# AINx3.net
KiCad netlist of a schematic drawn in EAGLE
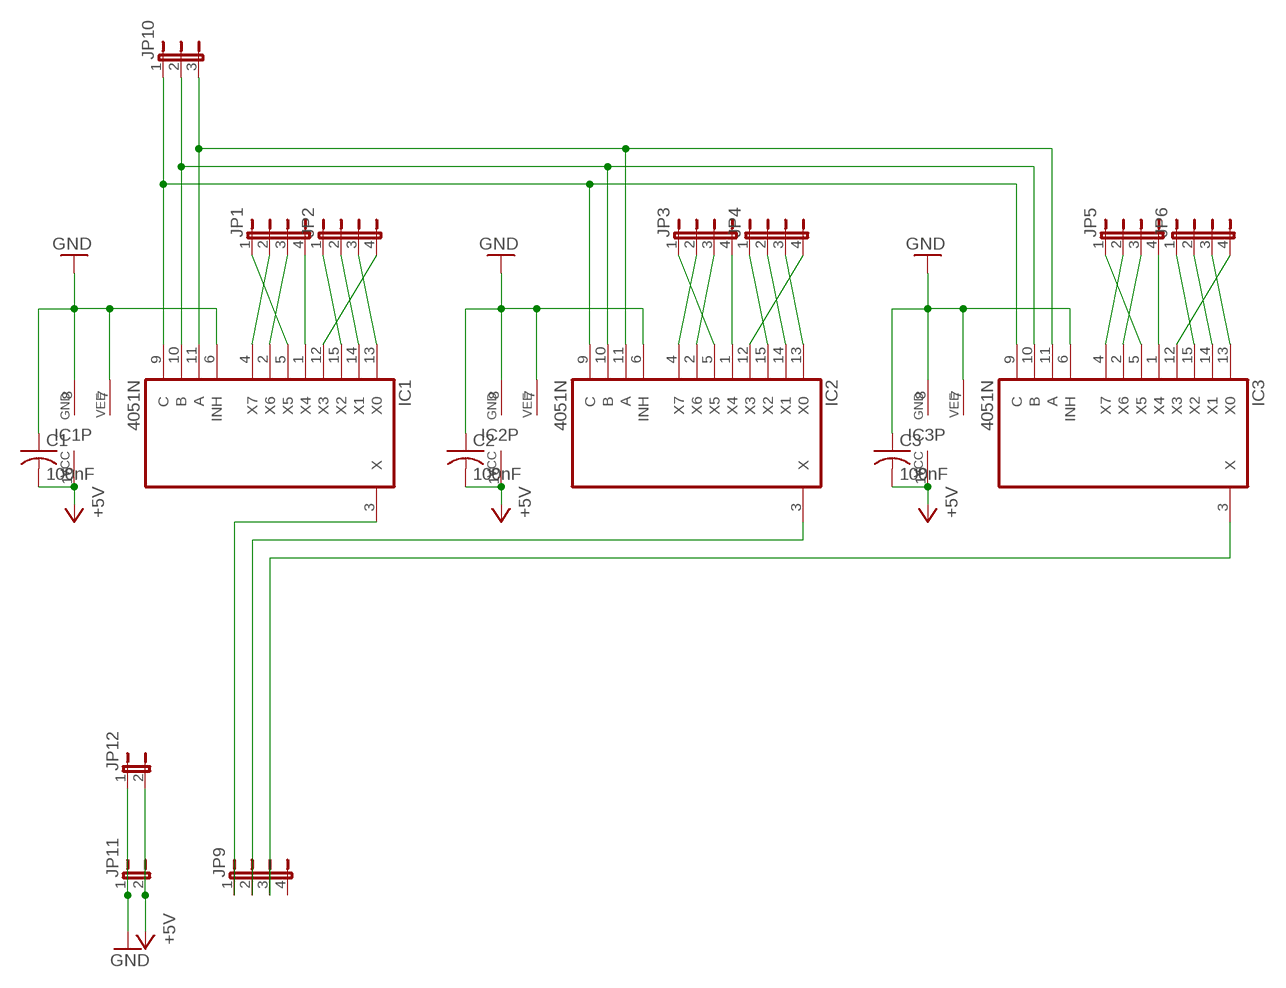
[diagram p0: schematic, sheet 1]

(export (version "E")
  (design (tool "Eeschema 10.0.6"))
  (components
    (comp (ref "C1")
      (value "100nF")
      (footprint "eagle-import:C025-025X050")
      (libsource (lib "eagle-import") (part "C-US025-025X050"))
    )
    (comp (ref "C2")
      (value "100nF")
      (footprint "eagle-import:C025-025X050")
      (libsource (lib "eagle-import") (part "C-US025-025X050"))
    )
    (comp (ref "C3")
      (value "100nF")
      (footprint "eagle-import:C025-025X050")
      (libsource (lib "eagle-import") (part "C-US025-025X050"))
    )
    (comp (ref "IC1")
      (value "4051N")
      (footprint "eagle-import:DIL16")
      (libsource (lib "eagle-import") (part "4051N"))
    )
    (comp (ref "IC2")
      (value "4051N")
      (footprint "eagle-import:DIL16")
      (libsource (lib "eagle-import") (part "4051N"))
    )
    (comp (ref "IC3")
      (value "4051N")
      (footprint "eagle-import:DIL16")
      (libsource (lib "eagle-import") (part "4051N"))
    )
    (comp (ref "JP1")
      (value "JP4E")
      (footprint "eagle-import:JP4")
      (libsource (lib "eagle-import") (part "JP4E"))
    )
    (comp (ref "JP2")
      (value "JP4E")
      (footprint "eagle-import:JP4")
      (libsource (lib "eagle-import") (part "JP4E"))
    )
    (comp (ref "JP3")
      (value "JP4E")
      (footprint "eagle-import:JP4")
      (libsource (lib "eagle-import") (part "JP4E"))
    )
    (comp (ref "JP4")
      (value "JP4E")
      (footprint "eagle-import:JP4")
      (libsource (lib "eagle-import") (part "JP4E"))
    )
    (comp (ref "JP5")
      (value "JP4E")
      (footprint "eagle-import:JP4")
      (libsource (lib "eagle-import") (part "JP4E"))
    )
    (comp (ref "JP6")
      (value "JP4E")
      (footprint "eagle-import:JP4")
      (libsource (lib "eagle-import") (part "JP4E"))
    )
    (comp (ref "JP9")
      (value "JP4E")
      (footprint "eagle-import:JP4")
      (libsource (lib "eagle-import") (part "JP4E"))
    )
    (comp (ref "JP10")
      (value "JP2E")
      (footprint "eagle-import:JP2")
      (libsource (lib "eagle-import") (part "JP2E"))
    )
    (comp (ref "JP11")
      (value "JP1E")
      (footprint "eagle-import:JP1")
      (libsource (lib "eagle-import") (part "JP1E"))
    )
    (comp (ref "JP12")
      (value "JP1E")
      (footprint "eagle-import:JP1")
      (libsource (lib "eagle-import") (part "JP1E"))
    )
  )
  (nets
    (net (code "1") (name "+5V") (class "Default")
      (node (ref "C1") (pin "2") (pinfunction "2_2") (pintype "passive"))
      (node (ref "C2") (pin "2") (pinfunction "2_2") (pintype "passive"))
      (node (ref "C3") (pin "2") (pinfunction "2_2") (pintype "passive"))
      (node (ref "IC1") (pin "16") (pinfunction "VCC_16") (pintype "power_in"))
      (node (ref "IC2") (pin "16") (pinfunction "VCC_16") (pintype "power_in"))
      (node (ref "IC3") (pin "16") (pinfunction "VCC_16") (pintype "power_in"))
      (node (ref "JP11") (pin "2") (pinfunction "2_2") (pintype "passive"))
      (node (ref "JP12") (pin "2") (pinfunction "2_2") (pintype "passive"))
    )
    (net (code "2") (name "GND") (class "Default")
      (node (ref "C1") (pin "1") (pinfunction "1_1") (pintype "passive"))
      (node (ref "C2") (pin "1") (pinfunction "1_1") (pintype "passive"))
      (node (ref "C3") (pin "1") (pinfunction "1_1") (pintype "passive"))
      (node (ref "IC1") (pin "6") (pinfunction "INH_6") (pintype "input"))
      (node (ref "IC1") (pin "7") (pinfunction "VEE_7") (pintype "power_in"))
      (node (ref "IC1") (pin "8") (pinfunction "GND_8") (pintype "power_in"))
      (node (ref "IC2") (pin "6") (pinfunction "INH_6") (pintype "input"))
      (node (ref "IC2") (pin "7") (pinfunction "VEE_7") (pintype "power_in"))
      (node (ref "IC2") (pin "8") (pinfunction "GND_8") (pintype "power_in"))
      (node (ref "IC3") (pin "6") (pinfunction "INH_6") (pintype "input"))
      (node (ref "IC3") (pin "7") (pinfunction "VEE_7") (pintype "power_in"))
      (node (ref "IC3") (pin "8") (pinfunction "GND_8") (pintype "power_in"))
      (node (ref "JP11") (pin "1") (pinfunction "1_1") (pintype "passive"))
      (node (ref "JP12") (pin "1") (pinfunction "1_1") (pintype "passive"))
    )
    (net (code "3") (name "Net-(IC1A-A)") (class "Default")
      (node (ref "IC1") (pin "11") (pinfunction "A_11") (pintype "input"))
      (node (ref "IC2") (pin "11") (pinfunction "A_11") (pintype "input"))
      (node (ref "IC3") (pin "11") (pinfunction "A_11") (pintype "input"))
      (node (ref "JP10") (pin "3") (pinfunction "3_3") (pintype "passive"))
    )
    (net (code "4") (name "Net-(IC1A-B)") (class "Default")
      (node (ref "IC1") (pin "10") (pinfunction "B_10") (pintype "input"))
      (node (ref "IC2") (pin "10") (pinfunction "B_10") (pintype "input"))
      (node (ref "IC3") (pin "10") (pinfunction "B_10") (pintype "input"))
      (node (ref "JP10") (pin "2") (pinfunction "2_2") (pintype "passive"))
    )
    (net (code "5") (name "Net-(IC1A-C)") (class "Default")
      (node (ref "IC1") (pin "9") (pinfunction "C_9") (pintype "input"))
      (node (ref "IC2") (pin "9") (pinfunction "C_9") (pintype "input"))
      (node (ref "IC3") (pin "9") (pinfunction "C_9") (pintype "input"))
      (node (ref "JP10") (pin "1") (pinfunction "1_1") (pintype "passive"))
    )
    (net (code "6") (name "Net-(IC1A-X)") (class "Default")
      (node (ref "IC1") (pin "3") (pinfunction "X_3") (pintype "bidirectional"))
      (node (ref "JP9") (pin "1") (pinfunction "1_1") (pintype "passive"))
    )
    (net (code "7") (name "Net-(IC1A-X0)") (class "Default")
      (node (ref "IC1") (pin "13") (pinfunction "X0_13") (pintype "bidirectional"))
      (node (ref "JP2") (pin "3") (pinfunction "3_3") (pintype "passive"))
    )
    (net (code "8") (name "Net-(IC1A-X1)") (class "Default")
      (node (ref "IC1") (pin "14") (pinfunction "X1_14") (pintype "bidirectional"))
      (node (ref "JP2") (pin "2") (pinfunction "2_2") (pintype "passive"))
    )
    (net (code "9") (name "Net-(IC1A-X2)") (class "Default")
      (node (ref "IC1") (pin "15") (pinfunction "X2_15") (pintype "bidirectional"))
      (node (ref "JP2") (pin "1") (pinfunction "1_1") (pintype "passive"))
    )
    (net (code "10") (name "Net-(IC1A-X3)") (class "Default")
      (node (ref "IC1") (pin "12") (pinfunction "X3_12") (pintype "bidirectional"))
      (node (ref "JP2") (pin "4") (pinfunction "4_4") (pintype "passive"))
    )
    (net (code "11") (name "Net-(IC1A-X4)") (class "Default")
      (node (ref "IC1") (pin "1") (pinfunction "X4_1") (pintype "bidirectional"))
      (node (ref "JP1") (pin "4") (pinfunction "4_4") (pintype "passive"))
    )
    (net (code "12") (name "Net-(IC1A-X5)") (class "Default")
      (node (ref "IC1") (pin "5") (pinfunction "X5_5") (pintype "bidirectional"))
      (node (ref "JP1") (pin "1") (pinfunction "1_1") (pintype "passive"))
    )
    (net (code "13") (name "Net-(IC1A-X6)") (class "Default")
      (node (ref "IC1") (pin "2") (pinfunction "X6_2") (pintype "bidirectional"))
      (node (ref "JP1") (pin "3") (pinfunction "3_3") (pintype "passive"))
    )
    (net (code "14") (name "Net-(IC1A-X7)") (class "Default")
      (node (ref "IC1") (pin "4") (pinfunction "X7_4") (pintype "bidirectional"))
      (node (ref "JP1") (pin "2") (pinfunction "2_2") (pintype "passive"))
    )
    (net (code "15") (name "Net-(IC2A-X)") (class "Default")
      (node (ref "IC2") (pin "3") (pinfunction "X_3") (pintype "bidirectional"))
      (node (ref "JP9") (pin "2") (pinfunction "2_2") (pintype "passive"))
    )
    (net (code "16") (name "Net-(IC2A-X0)") (class "Default")
      (node (ref "IC2") (pin "13") (pinfunction "X0_13") (pintype "bidirectional"))
      (node (ref "JP4") (pin "3") (pinfunction "3_3") (pintype "passive"))
    )
    (net (code "17") (name "Net-(IC2A-X1)") (class "Default")
      (node (ref "IC2") (pin "14") (pinfunction "X1_14") (pintype "bidirectional"))
      (node (ref "JP4") (pin "2") (pinfunction "2_2") (pintype "passive"))
    )
    (net (code "18") (name "Net-(IC2A-X2)") (class "Default")
      (node (ref "IC2") (pin "15") (pinfunction "X2_15") (pintype "bidirectional"))
      (node (ref "JP4") (pin "1") (pinfunction "1_1") (pintype "passive"))
    )
    (net (code "19") (name "Net-(IC2A-X3)") (class "Default")
      (node (ref "IC2") (pin "12") (pinfunction "X3_12") (pintype "bidirectional"))
      (node (ref "JP4") (pin "4") (pinfunction "4_4") (pintype "passive"))
    )
    (net (code "20") (name "Net-(IC2A-X4)") (class "Default")
      (node (ref "IC2") (pin "1") (pinfunction "X4_1") (pintype "bidirectional"))
      (node (ref "JP3") (pin "4") (pinfunction "4_4") (pintype "passive"))
    )
    (net (code "21") (name "Net-(IC2A-X5)") (class "Default")
      (node (ref "IC2") (pin "5") (pinfunction "X5_5") (pintype "bidirectional"))
      (node (ref "JP3") (pin "1") (pinfunction "1_1") (pintype "passive"))
    )
    (net (code "22") (name "Net-(IC2A-X6)") (class "Default")
      (node (ref "IC2") (pin "2") (pinfunction "X6_2") (pintype "bidirectional"))
      (node (ref "JP3") (pin "3") (pinfunction "3_3") (pintype "passive"))
    )
    (net (code "23") (name "Net-(IC2A-X7)") (class "Default")
      (node (ref "IC2") (pin "4") (pinfunction "X7_4") (pintype "bidirectional"))
      (node (ref "JP3") (pin "2") (pinfunction "2_2") (pintype "passive"))
    )
    (net (code "24") (name "Net-(IC3A-X)") (class "Default")
      (node (ref "IC3") (pin "3") (pinfunction "X_3") (pintype "bidirectional"))
      (node (ref "JP9") (pin "3") (pinfunction "3_3") (pintype "passive"))
    )
    (net (code "25") (name "Net-(IC3A-X0)") (class "Default")
      (node (ref "IC3") (pin "13") (pinfunction "X0_13") (pintype "bidirectional"))
      (node (ref "JP6") (pin "3") (pinfunction "3_3") (pintype "passive"))
    )
    (net (code "26") (name "Net-(IC3A-X1)") (class "Default")
      (node (ref "IC3") (pin "14") (pinfunction "X1_14") (pintype "bidirectional"))
      (node (ref "JP6") (pin "2") (pinfunction "2_2") (pintype "passive"))
    )
    (net (code "27") (name "Net-(IC3A-X2)") (class "Default")
      (node (ref "IC3") (pin "15") (pinfunction "X2_15") (pintype "bidirectional"))
      (node (ref "JP6") (pin "1") (pinfunction "1_1") (pintype "passive"))
    )
    (net (code "28") (name "Net-(IC3A-X3)") (class "Default")
      (node (ref "IC3") (pin "12") (pinfunction "X3_12") (pintype "bidirectional"))
      (node (ref "JP6") (pin "4") (pinfunction "4_4") (pintype "passive"))
    )
    (net (code "29") (name "Net-(IC3A-X4)") (class "Default")
      (node (ref "IC3") (pin "1") (pinfunction "X4_1") (pintype "bidirectional"))
      (node (ref "JP5") (pin "4") (pinfunction "4_4") (pintype "passive"))
    )
    (net (code "30") (name "Net-(IC3A-X5)") (class "Default")
      (node (ref "IC3") (pin "5") (pinfunction "X5_5") (pintype "bidirectional"))
      (node (ref "JP5") (pin "1") (pinfunction "1_1") (pintype "passive"))
    )
    (net (code "31") (name "Net-(IC3A-X6)") (class "Default")
      (node (ref "IC3") (pin "2") (pinfunction "X6_2") (pintype "bidirectional"))
      (node (ref "JP5") (pin "3") (pinfunction "3_3") (pintype "passive"))
    )
    (net (code "32") (name "Net-(IC3A-X7)") (class "Default")
      (node (ref "IC3") (pin "4") (pinfunction "X7_4") (pintype "bidirectional"))
      (node (ref "JP5") (pin "2") (pinfunction "2_2") (pintype "passive"))
    )
    (net (code "33") (name "unconnected-(JP9-Pad4)") (class "Default")
      (node (ref "JP9") (pin "4") (pinfunction "4_4") (pintype "passive"))
    )
  )
)
